# 08_Peripherral.net
KiCad netlist of a schematic drawn in Altium Designer
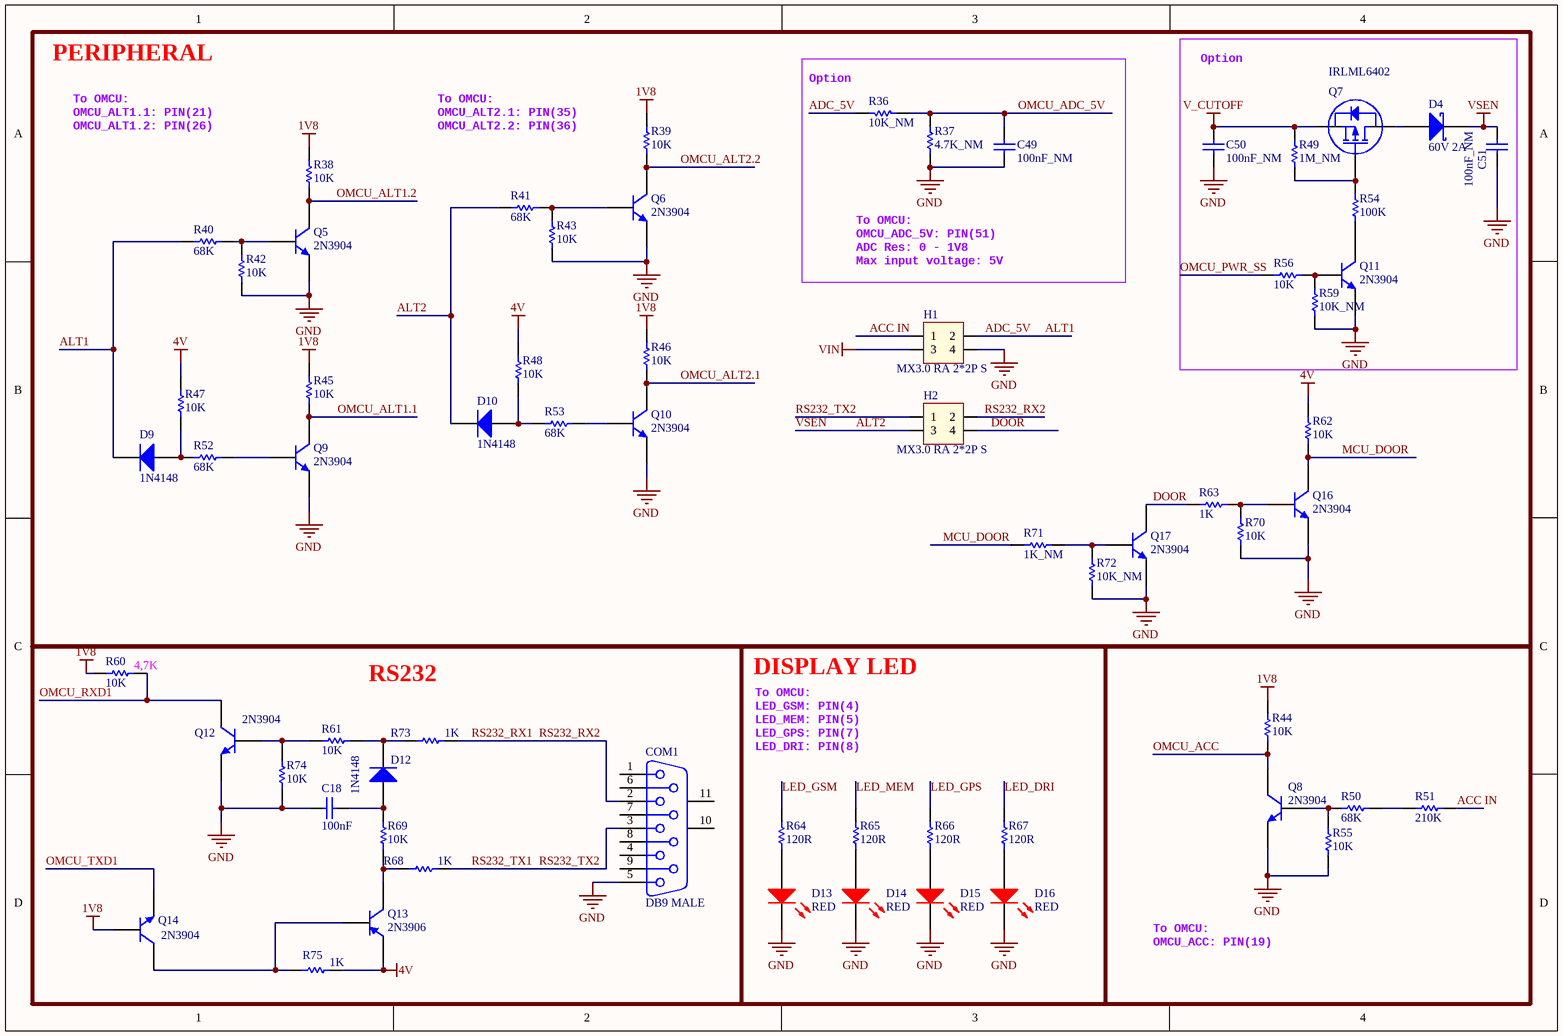
[diagram p0: 08 Peripherral.SchDoc]

(export (version "E")
  (design (tool "Eeschema 10.0.6"))
  (components
    (comp (ref "C18")
      (value "100nF")
      (footprint "0603 - C")
      (description "CAP CER 100nF 50V C0G/NP0 0603")
      (fields (field (name "MPN") "CL10C104JB8NNNC") (field (name "MFR") "SAMSUNG"))
      (libsource (lib "Library_Chip") (part "Cap 0603 100nF"))
    )
    (comp (ref "C49")
      (value "100nF_NM")
      (footprint "0603 - C")
      (description "CAP CER 100nF 50V C0G/NP0 0603")
      (fields (field (name "VOLTAGE") "50V") (field (name "MPN") "CL10C104JB8NNNC"))
      (libsource (lib "Library_Chip") (part "Cap 0603 100nF"))
    )
    (comp (ref "C50")
      (value "100nF_NM")
      (footprint "0603 - C")
      (description "CAP CER 100nF 50V C0G/NP0 0603")
      (fields (field (name "MPN") "CL10C104JB8NNNC") (field (name "MFR") "SAMSUNG"))
      (libsource (lib "Library_Chip") (part "Cap 0603 100nF"))
    )
    (comp (ref "C51")
      (value "100nF_NM")
      (footprint "0603 - C")
      (description "CAP CER 100nF 50V C0G/NP0 0603")
      (fields (field (name "MPN") "CL10C104JB8NNNC") (field (name "MFR") "SAMSUNG"))
      (libsource (lib "Library_Chip") (part "Cap 0603 100nF"))
    )
    (comp (ref "COM1")
      (value "DB9 MALE")
      (footprint "DSB 9M-SM")
      (description "CONN D-SUB PLUG 9POS PNL MNT")
      (fields (field (name "MPN") "772-E09-103R001") (field (name "MFR") "Norcomp Inc."))
      (libsource (lib "Library_ Connector") (part "DB9M S"))
    )
    (comp (ref "D4")
      (value "60V 2A")
      (footprint "SOD-123")
      (description "DIODE SCHOTTKY 60V 2A SOD123W")
      (fields (field (name "MPN") "PMEG6020ER,115") (field (name "MFR") "NXP"))
      (libsource (lib "Library_Chip") (part "Diode PMEG6020ER"))
    )
    (comp (ref "D9")
      (value "1N4148")
      (footprint "SOD-123")
      (description "DIODE GEN PURP 100V 300MA SOD123")
      (fields (field (name "MPN") "1N4148W-7-F") (field (name "MFR") "DIODES"))
      (libsource (lib "Library_Chip") (part "Diode 1N4148"))
    )
    (comp (ref "D10")
      (value "1N4148")
      (footprint "SOD-123")
      (description "DIODE GEN PURP 100V 300MA SOD123")
      (fields (field (name "MPN") "1N4148W-7-F") (field (name "MFR") "DIODES"))
      (libsource (lib "Library_Chip") (part "Diode 1N4148"))
    )
    (comp (ref "D12")
      (value "1N4148")
      (footprint "SOD-123")
      (description "DIODE GEN PURP 100V 300MA SOD123")
      (fields (field (name "MPN") "1N4148W-7-F") (field (name "MFR") "DIODES"))
      (libsource (lib "Library_Chip") (part "Diode 1N4148"))
    )
    (comp (ref "D13")
      (value "RED")
      (footprint "LED - 0603 - R")
      (description "LED RED CLEAR 0603 SMD")
      (fields (field (name "MFR") "Everlight") (field (name "MPN") "QTLP601CRTR"))
      (libsource (lib "Library_Chip") (part "LED 0603 RED"))
    )
    (comp (ref "D14")
      (value "RED")
      (footprint "LED - 0603 - R")
      (description "LED RED CLEAR 0603 SMD")
      (fields (field (name "MFR") "Everlight") (field (name "MPN") "QTLP601CRTR"))
      (libsource (lib "Library_Chip") (part "LED 0603 RED"))
    )
    (comp (ref "D15")
      (value "RED")
      (footprint "LED - 0603 - R")
      (description "LED RED CLEAR 0603 SMD")
      (fields (field (name "MFR") "Everlight") (field (name "MPN") "QTLP601CRTR"))
      (libsource (lib "Library_Chip") (part "LED 0603 RED"))
    )
    (comp (ref "D16")
      (value "RED")
      (footprint "LED - 0603 - R")
      (description "LED RED CLEAR 0603 SMD")
      (fields (field (name "MFR") "Everlight") (field (name "MPN") "QTLP601CRTR"))
      (libsource (lib "Library_Chip") (part "LED 0603 RED"))
    )
    (comp (ref "H1")
      (value "MX3.0 RA 2*2P S")
      (footprint "43045-M3045-2x2-B")
      (description "Micro-Fit 3.0™ Straight Header, 3.00mm Pitch, Dual Row, 4 Circuits")
      (fields (field (name "MPN") "M3045-2x2-B") (field (name "MFR") "China"))
      (libsource (lib "Library_ Connector") (part "HD2x2 S"))
    )
    (comp (ref "H2")
      (value "MX3.0 RA 2*2P S")
      (footprint "43045-M3045-2x2-B")
      (description "Micro-Fit 3.0™ Straight Header, 3.00mm Pitch, Dual Row, 4 Circuits")
      (fields (field (name "MPN") "M3045-2x2-B") (field (name "MFR") "China"))
      (libsource (lib "Library_ Connector") (part "HD2x2 S"))
    )
    (comp (ref "Q5")
      (value "2N3904")
      (footprint "SOT23B")
      (description "TRANS NPN 40V 0.2A SOT-23")
      (fields (field (name "MPN") "MMBT3904") (field (name "MFR") "Fairchild"))
      (libsource (lib "Library_Chip") (part "Transistor 2N3904"))
    )
    (comp (ref "Q6")
      (value "2N3904")
      (footprint "SOT23B")
      (description "TRANS NPN 40V 0.2A SOT-23")
      (fields (field (name "MPN") "MMBT3904") (field (name "MFR") "Fairchild"))
      (libsource (lib "Library_Chip") (part "Transistor 2N3904"))
    )
    (comp (ref "Q7")
      (value "IRLML6402")
      (footprint "SOT23B")
      (description "MOSFET P-CH 30V 3.6A SOT-23-3")
      (fields (field (name "MPN") "IRLML6402TRPBF") (field (name "MFR") "Infineon Technologies"))
      (libsource (lib "Library") (part "IRLML6402TRPBF"))
    )
    (comp (ref "Q8")
      (value "2N3904")
      (footprint "SOT23B")
      (description "TRANS NPN 40V 0.2A SOT-23")
      (fields (field (name "MPN") "MMBT3904") (field (name "MFR") "Fairchild"))
      (libsource (lib "Library_Chip") (part "Transistor 2N3904"))
    )
    (comp (ref "Q9")
      (value "2N3904")
      (footprint "SOT23B")
      (description "TRANS NPN 40V 0.2A SOT-23")
      (fields (field (name "MPN") "MMBT3904") (field (name "MFR") "Fairchild"))
      (libsource (lib "Library_Chip") (part "Transistor 2N3904"))
    )
    (comp (ref "Q10")
      (value "2N3904")
      (footprint "SOT23B")
      (description "TRANS NPN 40V 0.2A SOT-23")
      (fields (field (name "MPN") "MMBT3904") (field (name "MFR") "Fairchild"))
      (libsource (lib "Library_Chip") (part "Transistor 2N3904"))
    )
    (comp (ref "Q11")
      (value "2N3904")
      (footprint "SOT23B")
      (description "TRANS NPN 40V 0.2A SOT-23")
      (fields (field (name "MPN") "MMBT3904") (field (name "MFR") "Fairchild"))
      (libsource (lib "Library_Chip") (part "Transistor 2N3904"))
    )
    (comp (ref "Q12")
      (value "2N3904")
      (footprint "SOT23B")
      (description "TRANS NPN 40V 0.2A SOT-23")
      (fields (field (name "MPN") "MMBT3904") (field (name "MFR") "Fairchild"))
      (libsource (lib "Library_Chip") (part "Transistor 2N3904"))
    )
    (comp (ref "Q13")
      (value "2N3906")
      (footprint "SOT23B")
      (description "TRANS PNP 40V 0.2A SOT23")
      (fields (field (name "MPN") "MMBT3906") (field (name "MFR") "Fairchild"))
      (libsource (lib "Library_Chip") (part "Transistor 2N3906"))
    )
    (comp (ref "Q14")
      (value "2N3904")
      (footprint "SOT23B")
      (description "TRANS NPN 40V 0.2A SOT-23")
      (fields (field (name "MPN") "MMBT3904") (field (name "MFR") "Fairchild"))
      (libsource (lib "Library_Chip") (part "Transistor 2N3904"))
    )
    (comp (ref "Q16")
      (value "2N3904")
      (footprint "SOT23B")
      (description "TRANS NPN 40V 0.2A SOT-23")
      (fields (field (name "MPN") "MMBT3904") (field (name "MFR") "Fairchild"))
      (libsource (lib "Library_Chip") (part "Transistor 2N3904"))
    )
    (comp (ref "Q17")
      (value "2N3904")
      (footprint "SOT23B")
      (description "TRANS NPN 40V 0.2A SOT-23")
      (fields (field (name "MPN") "MMBT3904") (field (name "MFR") "Fairchild"))
      (libsource (lib "Library_Chip") (part "Transistor 2N3904"))
    )
    (comp (ref "R36")
      (value "10K_NM")
      (footprint "0603 - R")
      (description "RES SMD 10K OHM 1% 1/10W 0603")
      (fields (field (name "MFR") "Yageo") (field (name "MPN") "RC0603FR-0710KL"))
      (libsource (lib "Library_Chip") (part "Res 0603 10K"))
    )
    (comp (ref "R37")
      (value "4.7K_NM")
      (footprint "0603 - R")
      (description "RES SMD 4.7K OHM 1% 1/10W 0603")
      (fields (field (name "MFR") "Yageo") (field (name "MPN") "RC0603FR-074K7L"))
      (libsource (lib "Library_Chip") (part "Res 0603 4.7K"))
    )
    (comp (ref "R38")
      (value "10K")
      (footprint "0603 - R")
      (description "RES SMD 10K OHM 1% 1/10W 0603")
      (fields (field (name "MFR") "Yageo") (field (name "MPN") "RC0603FR-0710KL"))
      (libsource (lib "Library_Chip") (part "Res 0603 10K"))
    )
    (comp (ref "R39")
      (value "10K")
      (footprint "0603 - R")
      (description "RES SMD 10K OHM 1% 1/10W 0603")
      (fields (field (name "MFR") "Yageo") (field (name "MPN") "RC0603FR-0710KL"))
      (libsource (lib "Library_Chip") (part "Res 0603 10K"))
    )
    (comp (ref "R40")
      (value "68K")
      (footprint "0603 - R")
      (description "RES SMD 68K OHM 1% 1/10W 0603")
      (fields (field (name "MFR") "Yageo") (field (name "MPN") "RC0603FR-0768KL"))
      (libsource (lib "Library_Chip") (part "Res 0603 68K"))
    )
    (comp (ref "R41")
      (value "68K")
      (footprint "0603 - R")
      (description "RES SMD 68K OHM 1% 1/10W 0603")
      (fields (field (name "MFR") "Yageo") (field (name "MPN") "RC0603FR-0768KL"))
      (libsource (lib "Library_Chip") (part "Res 0603 68K"))
    )
    (comp (ref "R42")
      (value "10K")
      (footprint "0603 - R")
      (description "RES SMD 10K OHM 1% 1/10W 0603")
      (fields (field (name "MFR") "Yageo") (field (name "MPN") "RC0603FR-0710KL"))
      (libsource (lib "Library_Chip") (part "Res 0603 10K"))
    )
    (comp (ref "R43")
      (value "10K")
      (footprint "0603 - R")
      (description "RES SMD 10K OHM 1% 1/10W 0603")
      (fields (field (name "MFR") "Yageo") (field (name "MPN") "RC0603FR-0710KL"))
      (libsource (lib "Library_Chip") (part "Res 0603 10K"))
    )
    (comp (ref "R44")
      (value "10K")
      (footprint "0603 - R")
      (description "RES SMD 10K OHM 1% 1/10W 0603")
      (fields (field (name "MFR") "Yageo") (field (name "MPN") "RC0603FR-0710KL"))
      (libsource (lib "Library_Chip") (part "Res 0603 10K"))
    )
    (comp (ref "R45")
      (value "10K")
      (footprint "0603 - R")
      (description "RES SMD 10K OHM 1% 1/10W 0603")
      (fields (field (name "MFR") "Yageo") (field (name "MPN") "RC0603FR-0710KL"))
      (libsource (lib "Library_Chip") (part "Res 0603 10K"))
    )
    (comp (ref "R46")
      (value "10K")
      (footprint "0603 - R")
      (description "RES SMD 10K OHM 1% 1/10W 0603")
      (fields (field (name "MFR") "Yageo") (field (name "MPN") "RC0603FR-0710KL"))
      (libsource (lib "Library_Chip") (part "Res 0603 10K"))
    )
    (comp (ref "R47")
      (value "10K")
      (footprint "0603 - R")
      (description "RES SMD 10K OHM 1% 1/10W 0603")
      (fields (field (name "MFR") "Yageo") (field (name "MPN") "RC0603FR-0710KL"))
      (libsource (lib "Library_Chip") (part "Res 0603 10K"))
    )
    (comp (ref "R48")
      (value "10K")
      (footprint "0603 - R")
      (description "RES SMD 10K OHM 1% 1/10W 0603")
      (fields (field (name "MFR") "Yageo") (field (name "MPN") "RC0603FR-0710KL"))
      (libsource (lib "Library_Chip") (part "Res 0603 10K"))
    )
    (comp (ref "R49")
      (value "1M_NM")
      (footprint "0603 - R")
      (description "RES SMD 1M OHM 1% 1/10W 0603")
      (fields (field (name "MFR") "Yageo") (field (name "MPN") "RC0603FR-071ML"))
      (libsource (lib "Library_Chip") (part "Res 0603 1M"))
    )
    (comp (ref "R50")
      (value "68K")
      (footprint "0603 - R")
      (description "RES SMD 68K OHM 1% 1/10W 0603")
      (fields (field (name "MFR") "Yageo") (field (name "MPN") "RC0603FR-0768KL"))
      (libsource (lib "Library_Chip") (part "Res 0603 68K"))
    )
    (comp (ref "R51")
      (value "210K")
      (footprint "0603 - R")
      (description "RES SMD 210K OHM 1% 1/10W 0603")
      (fields (field (name "MFR") "Yageo") (field (name "MPN") "RC0603FR-07210KL"))
      (libsource (lib "Library_Chip") (part "Res 0603 210K"))
    )
    (comp (ref "R52")
      (value "68K")
      (footprint "0603 - R")
      (description "RES SMD 68K OHM 1% 1/10W 0603")
      (fields (field (name "MFR") "Yageo") (field (name "MPN") "RC0603FR-0768KL"))
      (libsource (lib "Library_Chip") (part "Res 0603 68K"))
    )
    (comp (ref "R53")
      (value "68K")
      (footprint "0603 - R")
      (description "RES SMD 68K OHM 1% 1/10W 0603")
      (fields (field (name "MFR") "Yageo") (field (name "MPN") "RC0603FR-0768KL"))
      (libsource (lib "Library_Chip") (part "Res 0603 68K"))
    )
    (comp (ref "R54")
      (value "100K")
      (footprint "0603 - R")
      (description "RES SMD 100K OHM 1% 1/10W 0603")
      (fields (field (name "MFR") "Yageo") (field (name "MPN") "RC0603FR-07100KL"))
      (libsource (lib "Library_Chip") (part "Res 0603 100K"))
    )
    (comp (ref "R55")
      (value "10K")
      (footprint "0603 - R")
      (description "RES SMD 10K OHM 1% 1/10W 0603")
      (fields (field (name "MFR") "Yageo") (field (name "MPN") "RC0603FR-0710KL"))
      (libsource (lib "Library_Chip") (part "Res 0603 10K"))
    )
    (comp (ref "R56")
      (value "10K")
      (footprint "0603 - R")
      (description "RES SMD 10K OHM 1% 1/10W 0603")
      (fields (field (name "MFR") "Yageo") (field (name "MPN") "RC0603FR-0710KL"))
      (libsource (lib "Library_Chip") (part "Res 0603 10K"))
    )
    (comp (ref "R59")
      (value "10K_NM")
      (footprint "0603 - R")
      (description "RES SMD 10K OHM 1% 1/10W 0603")
      (fields (field (name "MFR") "Yageo") (field (name "MPN") "RC0603FR-0710KL"))
      (libsource (lib "Library_Chip") (part "Res 0603 10K"))
    )
    (comp (ref "R60")
      (value "10K")
      (footprint "0603 - R")
      (description "RES SMD 10K OHM 1% 1/10W 0603")
      (fields (field (name "MFR") "Yageo") (field (name "MPN") "RC0603FR-0710KL"))
      (libsource (lib "Library_Chip") (part "Res 0603 10K"))
    )
    (comp (ref "R61")
      (value "10K")
      (footprint "0603 - R")
      (description "RES SMD 10K OHM 1% 1/10W 0603")
      (fields (field (name "MFR") "Yageo") (field (name "MPN") "RC0603FR-0710KL"))
      (libsource (lib "Library_Chip") (part "Res 0603 10K"))
    )
    (comp (ref "R62")
      (value "10K")
      (footprint "0603 - R")
      (description "RES SMD 10K OHM 1% 1/10W 0603")
      (fields (field (name "MFR") "Yageo") (field (name "MPN") "RC0603FR-0710KL"))
      (libsource (lib "Library_Chip") (part "Res 0603 10K"))
    )
    (comp (ref "R63")
      (value "1K")
      (footprint "0603 - R")
      (description "RES SMD 1K OHM 1% 1/10W 0603")
      (fields (field (name "MFR") "Yageo") (field (name "MPN") "RC0603FR-071KL"))
      (libsource (lib "Library_Chip") (part "Res 0603 1K"))
    )
    (comp (ref "R64")
      (value "120R")
      (footprint "0603 - R")
      (description "RES SMD 120 OHM 1% 1/10W 0603")
      (fields (field (name "MFR") "Yageo") (field (name "MPN") "AF0603FR-07120RL"))
      (libsource (lib "Library_Chip") (part "Res 0603 120R"))
    )
    (comp (ref "R65")
      (value "120R")
      (footprint "0603 - R")
      (description "RES SMD 120 OHM 1% 1/10W 0603")
      (fields (field (name "MFR") "Yageo") (field (name "MPN") "AF0603FR-07120RL"))
      (libsource (lib "Library_Chip") (part "Res 0603 120R"))
    )
    (comp (ref "R66")
      (value "120R")
      (footprint "0603 - R")
      (description "RES SMD 120 OHM 1% 1/10W 0603")
      (fields (field (name "MFR") "Yageo") (field (name "MPN") "AF0603FR-07120RL"))
      (libsource (lib "Library_Chip") (part "Res 0603 120R"))
    )
    (comp (ref "R67")
      (value "120R")
      (footprint "0603 - R")
      (description "RES SMD 120 OHM 1% 1/10W 0603")
      (fields (field (name "MFR") "Yageo") (field (name "MPN") "AF0603FR-07120RL"))
      (libsource (lib "Library_Chip") (part "Res 0603 120R"))
    )
    (comp (ref "R68")
      (value "1K")
      (footprint "0603 - R")
      (description "RES SMD 1K OHM 1% 1/10W 0603")
      (fields (field (name "MFR") "Yageo") (field (name "MPN") "RC0603FR-071KL"))
      (libsource (lib "Library_Chip") (part "Res 0603 1K"))
    )
    (comp (ref "R69")
      (value "10K")
      (footprint "0603 - R")
      (description "RES SMD 10K OHM 1% 1/10W 0603")
      (fields (field (name "MFR") "Yageo") (field (name "MPN") "RC0603FR-0710KL"))
      (libsource (lib "Library_Chip") (part "Res 0603 10K"))
    )
    (comp (ref "R70")
      (value "10K")
      (footprint "0603 - R")
      (description "RES SMD 10K OHM 1% 1/10W 0603")
      (fields (field (name "MFR") "Yageo") (field (name "MPN") "RC0603FR-0710KL"))
      (libsource (lib "Library_Chip") (part "Res 0603 10K"))
    )
    (comp (ref "R71")
      (value "1K_NM")
      (footprint "0603 - R")
      (description "RES SMD 1K OHM 1% 1/10W 0603")
      (fields (field (name "MFR") "Yageo") (field (name "MPN") "RC0603FR-071KL"))
      (libsource (lib "Library_Chip") (part "Res 0603 1K"))
    )
    (comp (ref "R72")
      (value "10K_NM")
      (footprint "0603 - R")
      (description "RES SMD 10K OHM 1% 1/10W 0603")
      (fields (field (name "MFR") "Yageo") (field (name "MPN") "RC0603FR-0710KL"))
      (libsource (lib "Library_Chip") (part "Res 0603 10K"))
    )
    (comp (ref "R73")
      (value "1K")
      (footprint "0603 - R")
      (description "RES SMD 1K OHM 1% 1/10W 0603")
      (fields (field (name "MFR") "Yageo") (field (name "MPN") "RC0603FR-071KL"))
      (libsource (lib "Library_Chip") (part "Res 0603 1K"))
    )
    (comp (ref "R74")
      (value "10K")
      (footprint "0603 - R")
      (description "RES SMD 10K OHM 1% 1/10W 0603")
      (fields (field (name "MFR") "Yageo") (field (name "MPN") "RC0603FR-0710KL"))
      (libsource (lib "Library_Chip") (part "Res 0603 10K"))
    )
    (comp (ref "R75")
      (value "1K")
      (footprint "0603 - R")
      (description "RES SMD 1K OHM 1% 1/10W 0603")
      (fields (field (name "MFR") "Yageo") (field (name "MPN") "RC0603FR-071KL"))
      (libsource (lib "Library_Chip") (part "Res 0603 1K"))
    )
  )
  (nets
    (net (code "1") (name "/ACC IN") (class "Default")
      (node (ref "H1") (pin "1") (pinfunction "1_1") (pintype "passive"))
      (node (ref "R51") (pin "1") (pinfunction "1_1") (pintype "passive"))
    )
    (net (code "2") (name "/ADC_5V") (class "Default")
      (node (ref "D9") (pin "2") (pinfunction "K_2") (pintype "passive"))
      (node (ref "H1") (pin "2") (pinfunction "2_2") (pintype "passive"))
      (node (ref "R36") (pin "2") (pinfunction "2_2") (pintype "passive"))
      (node (ref "R40") (pin "1") (pinfunction "1_1") (pintype "passive"))
    )
    (net (code "3") (name "/DOOR") (class "Default")
      (node (ref "H2") (pin "4") (pinfunction "4_4") (pintype "passive"))
      (node (ref "Q17") (pin "3") (pinfunction "C_3") (pintype "passive"))
      (node (ref "R63") (pin "1") (pinfunction "1_1") (pintype "passive"))
    )
    (net (code "4") (name "/LED_DRI") (class "Default")
      (node (ref "R67") (pin "2") (pinfunction "2_2") (pintype "passive"))
    )
    (net (code "5") (name "/LED_GPS") (class "Default")
      (node (ref "R66") (pin "2") (pinfunction "2_2") (pintype "passive"))
    )
    (net (code "6") (name "/LED_GSM") (class "Default")
      (node (ref "R64") (pin "2") (pinfunction "2_2") (pintype "passive"))
    )
    (net (code "7") (name "/LED_MEM") (class "Default")
      (node (ref "R65") (pin "2") (pinfunction "2_2") (pintype "passive"))
    )
    (net (code "8") (name "/MCU_DOOR") (class "Default")
      (node (ref "Q16") (pin "3") (pinfunction "C_3") (pintype "passive"))
      (node (ref "R62") (pin "1") (pinfunction "1_1") (pintype "passive"))
      (node (ref "R71") (pin "1") (pinfunction "1_1") (pintype "passive"))
    )
    (net (code "9") (name "/OMCU_ACC") (class "Default")
      (node (ref "Q8") (pin "3") (pinfunction "C_3") (pintype "passive"))
      (node (ref "R44") (pin "1") (pinfunction "1_1") (pintype "passive"))
    )
    (net (code "10") (name "/OMCU_ADC_5V") (class "Default")
      (node (ref "C49") (pin "2") (pinfunction "2_2") (pintype "passive"))
      (node (ref "R36") (pin "1") (pinfunction "1_1") (pintype "passive"))
      (node (ref "R37") (pin "2") (pinfunction "2_2") (pintype "passive"))
    )
    (net (code "11") (name "/OMCU_ALT1.1") (class "Default")
      (node (ref "Q9") (pin "3") (pinfunction "C_3") (pintype "passive"))
      (node (ref "R45") (pin "1") (pinfunction "1_1") (pintype "passive"))
    )
    (net (code "12") (name "/OMCU_ALT1.2") (class "Default")
      (node (ref "Q5") (pin "3") (pinfunction "C_3") (pintype "passive"))
      (node (ref "R38") (pin "1") (pinfunction "1_1") (pintype "passive"))
    )
    (net (code "13") (name "/OMCU_ALT2.1") (class "Default")
      (node (ref "Q10") (pin "3") (pinfunction "C_3") (pintype "passive"))
      (node (ref "R46") (pin "1") (pinfunction "1_1") (pintype "passive"))
    )
    (net (code "14") (name "/OMCU_ALT2.2") (class "Default")
      (node (ref "Q6") (pin "3") (pinfunction "C_3") (pintype "passive"))
      (node (ref "R39") (pin "1") (pinfunction "1_1") (pintype "passive"))
    )
    (net (code "15") (name "/OMCU_PWR_SS") (class "Default")
      (node (ref "R56") (pin "1") (pinfunction "1_1") (pintype "passive"))
    )
    (net (code "16") (name "/OMCU_RXD1") (class "Default")
      (node (ref "Q12") (pin "3") (pinfunction "C_3") (pintype "passive"))
      (node (ref "R60") (pin "1") (pinfunction "1_1") (pintype "passive"))
    )
    (net (code "17") (name "/OMCU_TXD1") (class "Default")
      (node (ref "Q14") (pin "2") (pinfunction "E_2") (pintype "passive"))
    )
    (net (code "18") (name "/RS232_RX1") (class "Default")
      (node (ref "COM1") (pin "2") (pinfunction "2_2") (pintype "passive"))
      (node (ref "H2") (pin "2") (pinfunction "2_2") (pintype "passive"))
      (node (ref "R73") (pin "2") (pinfunction "2_2") (pintype "passive"))
    )
    (net (code "19") (name "/RS232_TX1") (class "Default")
      (node (ref "COM1") (pin "3") (pinfunction "3_3") (pintype "passive"))
      (node (ref "H2") (pin "1") (pinfunction "1_1") (pintype "passive"))
      (node (ref "R68") (pin "2") (pinfunction "2_2") (pintype "passive"))
    )
    (net (code "20") (name "1V8") (class "Default")
      (node (ref "Q14") (pin "1") (pinfunction "B_1") (pintype "passive"))
      (node (ref "R38") (pin "2") (pinfunction "2_2") (pintype "passive"))
      (node (ref "R39") (pin "2") (pinfunction "2_2") (pintype "passive"))
      (node (ref "R44") (pin "2") (pinfunction "2_2") (pintype "passive"))
      (node (ref "R45") (pin "2") (pinfunction "2_2") (pintype "passive"))
      (node (ref "R46") (pin "2") (pinfunction "2_2") (pintype "passive"))
      (node (ref "R60") (pin "2") (pinfunction "2_2") (pintype "passive"))
    )
    (net (code "21") (name "4V") (class "Default")
      (node (ref "Q13") (pin "2") (pinfunction "E_2") (pintype "passive"))
      (node (ref "R47") (pin "2") (pinfunction "2_2") (pintype "passive"))
      (node (ref "R48") (pin "2") (pinfunction "2_2") (pintype "passive"))
      (node (ref "R62") (pin "2") (pinfunction "2_2") (pintype "passive"))
      (node (ref "R75") (pin "2") (pinfunction "2_2") (pintype "passive"))
    )
    (net (code "22") (name "GND") (class "Default")
      (node (ref "C18") (pin "1") (pinfunction "1_1") (pintype "passive"))
      (node (ref "C49") (pin "1") (pinfunction "1_1") (pintype "passive"))
      (node (ref "C50") (pin "1") (pinfunction "1_1") (pintype "passive"))
      (node (ref "C51") (pin "1") (pinfunction "1_1") (pintype "passive"))
      (node (ref "COM1") (pin "5") (pinfunction "5_5") (pintype "passive"))
      (node (ref "D13") (pin "2") (pinfunction "K_2") (pintype "passive"))
      (node (ref "D14") (pin "2") (pinfunction "K_2") (pintype "passive"))
      (node (ref "D15") (pin "2") (pinfunction "K_2") (pintype "passive"))
      (node (ref "D16") (pin "2") (pinfunction "K_2") (pintype "passive"))
      (node (ref "H1") (pin "4") (pinfunction "4_4") (pintype "passive"))
      (node (ref "Q10") (pin "2") (pinfunction "E_2") (pintype "passive"))
      (node (ref "Q11") (pin "2") (pinfunction "E_2") (pintype "passive"))
      (node (ref "Q12") (pin "2") (pinfunction "E_2") (pintype "passive"))
      (node (ref "Q16") (pin "2") (pinfunction "E_2") (pintype "passive"))
      (node (ref "Q17") (pin "2") (pinfunction "E_2") (pintype "passive"))
      (node (ref "Q5") (pin "2") (pinfunction "E_2") (pintype "passive"))
      (node (ref "Q6") (pin "2") (pinfunction "E_2") (pintype "passive"))
      (node (ref "Q8") (pin "2") (pinfunction "E_2") (pintype "passive"))
      (node (ref "Q9") (pin "2") (pinfunction "E_2") (pintype "passive"))
      (node (ref "R37") (pin "1") (pinfunction "1_1") (pintype "passive"))
      (node (ref "R42") (pin "1") (pinfunction "1_1") (pintype "passive"))
      (node (ref "R43") (pin "1") (pinfunction "1_1") (pintype "passive"))
      (node (ref "R55") (pin "2") (pinfunction "2_2") (pintype "passive"))
      (node (ref "R59") (pin "1") (pinfunction "1_1") (pintype "passive"))
      (node (ref "R70") (pin "1") (pinfunction "1_1") (pintype "passive"))
      (node (ref "R72") (pin "1") (pinfunction "1_1") (pintype "passive"))
      (node (ref "R74") (pin "2") (pinfunction "2_2") (pintype "passive"))
    )
    (net (code "23") (name "Net-(D4-A)") (class "Default")
      (node (ref "D4") (pin "1") (pinfunction "A_1") (pintype "passive"))
      (node (ref "Q7") (pin "3") (pinfunction "D_3") (pintype "passive"))
    )
    (net (code "24") (name "Net-(D9-A)") (class "Default")
      (node (ref "D9") (pin "1") (pinfunction "A_1") (pintype "passive"))
      (node (ref "R47") (pin "1") (pinfunction "1_1") (pintype "passive"))
      (node (ref "R52") (pin "1") (pinfunction "1_1") (pintype "passive"))
    )
    (net (code "25") (name "Net-(D10-A)") (class "Default")
      (node (ref "D10") (pin "1") (pinfunction "A_1") (pintype "passive"))
      (node (ref "R48") (pin "1") (pinfunction "1_1") (pintype "passive"))
      (node (ref "R53") (pin "1") (pinfunction "1_1") (pintype "passive"))
    )
    (net (code "26") (name "Net-(D12-A)") (class "Default")
      (node (ref "C18") (pin "2") (pinfunction "2_2") (pintype "passive"))
      (node (ref "D12") (pin "1") (pinfunction "A_1") (pintype "passive"))
      (node (ref "R69") (pin "1") (pinfunction "1_1") (pintype "passive"))
    )
    (net (code "27") (name "Net-(D12-K)") (class "Default")
      (node (ref "D12") (pin "2") (pinfunction "K_2") (pintype "passive"))
      (node (ref "R61") (pin "1") (pinfunction "1_1") (pintype "passive"))
      (node (ref "R73") (pin "1") (pinfunction "1_1") (pintype "passive"))
    )
    (net (code "28") (name "Net-(D13-A)") (class "Default")
      (node (ref "D13") (pin "1") (pinfunction "A_1") (pintype "passive"))
      (node (ref "R64") (pin "1") (pinfunction "1_1") (pintype "passive"))
    )
    (net (code "29") (name "Net-(D14-A)") (class "Default")
      (node (ref "D14") (pin "1") (pinfunction "A_1") (pintype "passive"))
      (node (ref "R65") (pin "1") (pinfunction "1_1") (pintype "passive"))
    )
    (net (code "30") (name "Net-(D15-A)") (class "Default")
      (node (ref "D15") (pin "1") (pinfunction "A_1") (pintype "passive"))
      (node (ref "R66") (pin "1") (pinfunction "1_1") (pintype "passive"))
    )
    (net (code "31") (name "Net-(D16-A)") (class "Default")
      (node (ref "D16") (pin "1") (pinfunction "A_1") (pintype "passive"))
      (node (ref "R67") (pin "1") (pinfunction "1_1") (pintype "passive"))
    )
    (net (code "32") (name "Net-(Q5-B)") (class "Default")
      (node (ref "Q5") (pin "1") (pinfunction "B_1") (pintype "passive"))
      (node (ref "R40") (pin "2") (pinfunction "2_2") (pintype "passive"))
      (node (ref "R42") (pin "2") (pinfunction "2_2") (pintype "passive"))
    )
    (net (code "33") (name "Net-(Q6-B)") (class "Default")
      (node (ref "Q6") (pin "1") (pinfunction "B_1") (pintype "passive"))
      (node (ref "R41") (pin "2") (pinfunction "2_2") (pintype "passive"))
      (node (ref "R43") (pin "2") (pinfunction "2_2") (pintype "passive"))
    )
    (net (code "34") (name "Net-(Q7-G)") (class "Default")
      (node (ref "Q7") (pin "1") (pinfunction "G_1") (pintype "passive"))
      (node (ref "R49") (pin "1") (pinfunction "1_1") (pintype "passive"))
      (node (ref "R54") (pin "2") (pinfunction "2_2") (pintype "passive"))
    )
    (net (code "35") (name "Net-(Q8-B)") (class "Default")
      (node (ref "Q8") (pin "1") (pinfunction "B_1") (pintype "passive"))
      (node (ref "R50") (pin "1") (pinfunction "1_1") (pintype "passive"))
      (node (ref "R55") (pin "1") (pinfunction "1_1") (pintype "passive"))
    )
    (net (code "36") (name "Net-(Q9-B)") (class "Default")
      (node (ref "Q9") (pin "1") (pinfunction "B_1") (pintype "passive"))
      (node (ref "R52") (pin "2") (pinfunction "2_2") (pintype "passive"))
    )
    (net (code "37") (name "Net-(Q10-B)") (class "Default")
      (node (ref "Q10") (pin "1") (pinfunction "B_1") (pintype "passive"))
      (node (ref "R53") (pin "2") (pinfunction "2_2") (pintype "passive"))
    )
    (net (code "38") (name "Net-(Q11-B)") (class "Default")
      (node (ref "Q11") (pin "1") (pinfunction "B_1") (pintype "passive"))
      (node (ref "R56") (pin "2") (pinfunction "2_2") (pintype "passive"))
      (node (ref "R59") (pin "2") (pinfunction "2_2") (pintype "passive"))
    )
    (net (code "39") (name "Net-(Q11-C)") (class "Default")
      (node (ref "Q11") (pin "3") (pinfunction "C_3") (pintype "passive"))
      (node (ref "R54") (pin "1") (pinfunction "1_1") (pintype "passive"))
    )
    (net (code "40") (name "Net-(Q12-B)") (class "Default")
      (node (ref "Q12") (pin "1") (pinfunction "B_1") (pintype "passive"))
      (node (ref "R61") (pin "2") (pinfunction "2_2") (pintype "passive"))
      (node (ref "R74") (pin "1") (pinfunction "1_1") (pintype "passive"))
    )
    (net (code "41") (name "Net-(Q13-B)") (class "Default")
      (node (ref "Q13") (pin "1") (pinfunction "B_1") (pintype "passive"))
      (node (ref "Q14") (pin "3") (pinfunction "C_3") (pintype "passive"))
      (node (ref "R75") (pin "1") (pinfunction "1_1") (pintype "passive"))
    )
    (net (code "42") (name "Net-(Q13-C)") (class "Default")
      (node (ref "Q13") (pin "3") (pinfunction "C_3") (pintype "passive"))
      (node (ref "R68") (pin "1") (pinfunction "1_1") (pintype "passive"))
      (node (ref "R69") (pin "2") (pinfunction "2_2") (pintype "passive"))
    )
    (net (code "43") (name "Net-(Q16-B)") (class "Default")
      (node (ref "Q16") (pin "1") (pinfunction "B_1") (pintype "passive"))
      (node (ref "R63") (pin "2") (pinfunction "2_2") (pintype "passive"))
      (node (ref "R70") (pin "2") (pinfunction "2_2") (pintype "passive"))
    )
    (net (code "44") (name "Net-(Q17-B)") (class "Default")
      (node (ref "Q17") (pin "1") (pinfunction "B_1") (pintype "passive"))
      (node (ref "R71") (pin "2") (pinfunction "2_2") (pintype "passive"))
      (node (ref "R72") (pin "2") (pinfunction "2_2") (pintype "passive"))
    )
    (net (code "45") (name "Net-(R50-Pad2)") (class "Default")
      (node (ref "R50") (pin "2") (pinfunction "2_2") (pintype "passive"))
      (node (ref "R51") (pin "2") (pinfunction "2_2") (pintype "passive"))
    )
    (net (code "46") (name "VIN") (class "Default")
      (node (ref "H1") (pin "3") (pinfunction "3_3") (pintype "passive"))
    )
    (net (code "47") (name "VSEN") (class "Default")
      (node (ref "C51") (pin "2") (pinfunction "2_2") (pintype "passive"))
      (node (ref "D10") (pin "2") (pinfunction "K_2") (pintype "passive"))
      (node (ref "D4") (pin "2") (pinfunction "K_2") (pintype "passive"))
      (node (ref "H2") (pin "3") (pinfunction "3_3") (pintype "passive"))
      (node (ref "R41") (pin "1") (pinfunction "1_1") (pintype "passive"))
    )
    (net (code "48") (name "V_CUTOFF") (class "Default")
      (node (ref "C50") (pin "2") (pinfunction "2_2") (pintype "passive"))
      (node (ref "Q7") (pin "2") (pinfunction "S_2") (pintype "passive"))
      (node (ref "R49") (pin "2") (pinfunction "2_2") (pintype "passive"))
    )
    (net (code "49") (name "unconnected-(COM1-MH1-Pad10)") (class "Default")
      (node (ref "COM1") (pin "10") (pinfunction "MH1_10") (pintype "passive"))
    )
    (net (code "50") (name "unconnected-(COM1-MH2-Pad11)") (class "Default")
      (node (ref "COM1") (pin "11") (pinfunction "MH2_11") (pintype "passive"))
    )
    (net (code "51") (name "unconnected-(COM1-Pad1)") (class "Default")
      (node (ref "COM1") (pin "1") (pinfunction "1_1") (pintype "passive"))
    )
    (net (code "52") (name "unconnected-(COM1-Pad4)") (class "Default")
      (node (ref "COM1") (pin "4") (pinfunction "4_4") (pintype "passive"))
    )
    (net (code "53") (name "unconnected-(COM1-Pad6)") (class "Default")
      (node (ref "COM1") (pin "6") (pinfunction "6_6") (pintype "passive"))
    )
    (net (code "54") (name "unconnected-(COM1-Pad7)") (class "Default")
      (node (ref "COM1") (pin "7") (pinfunction "7_7") (pintype "passive"))
    )
    (net (code "55") (name "unconnected-(COM1-Pad8)") (class "Default")
      (node (ref "COM1") (pin "8") (pinfunction "8_8") (pintype "passive"))
    )
    (net (code "56") (name "unconnected-(COM1-Pad9)") (class "Default")
      (node (ref "COM1") (pin "9") (pinfunction "9_9") (pintype "passive"))
    )
  )
)
